# RJ45_Sheet.net
KiCad netlist of a schematic drawn in Altium Designer
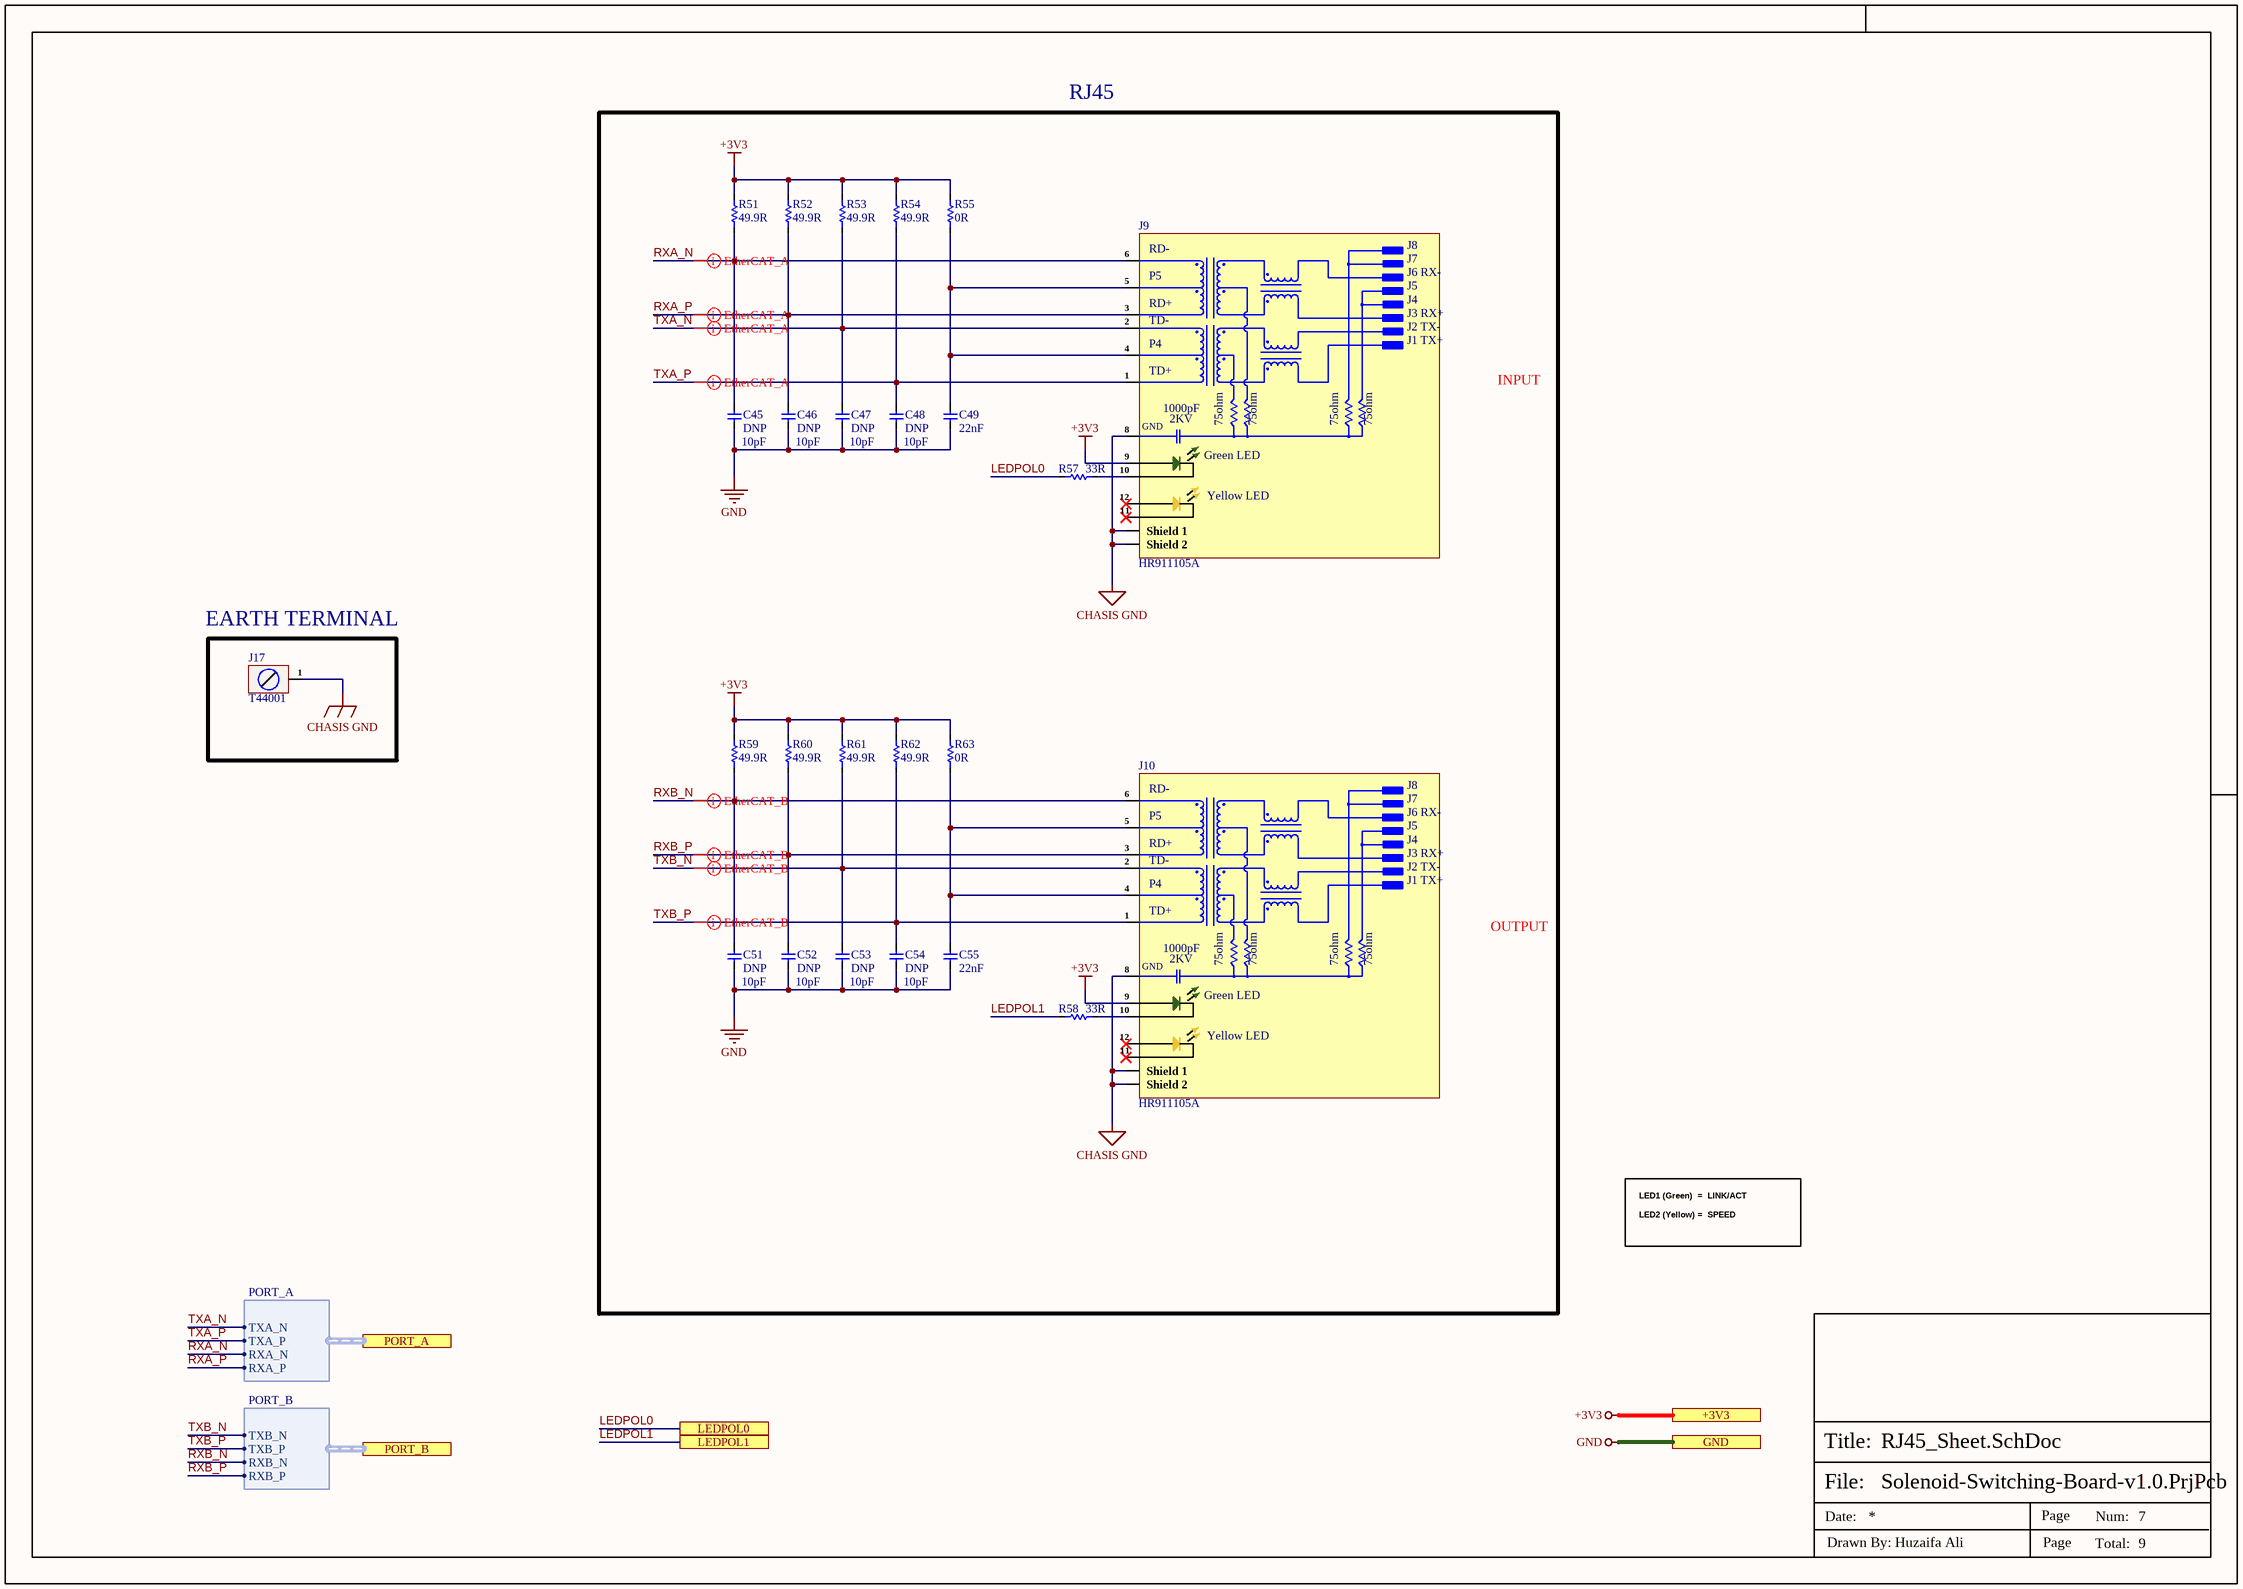
[diagram p0: RJ45_Sheet.SchDoc]

(export (version "E")
  (design (tool "Eeschema 10.0.6"))
  (components
    (comp (ref "C45")
      (value "DNP")
      (footprint "Cap-0402")
      (description "CAP CER 10PF 50V C0G/NP0 0402")
      (fields
        (field (name "MANUFACTURER") "Murata")
        (field (name "MANUFACTURER PART NUMBER") "GRM1555C1H100JA01D")
      )
      (libsource (lib "eSpark Libraries") (part "GRM1555C1H100JA01D"))
    )
    (comp (ref "C46")
      (value "DNP")
      (footprint "Cap-0402")
      (description "CAP CER 10PF 50V C0G/NP0 0402")
      (fields
        (field (name "MANUFACTURER") "Murata")
        (field (name "MANUFACTURER PART NUMBER") "GRM1555C1H100JA01D")
      )
      (libsource (lib "eSpark Libraries") (part "GRM1555C1H100JA01D"))
    )
    (comp (ref "C47")
      (value "DNP")
      (footprint "Cap-0402")
      (description "CAP CER 10PF 50V C0G/NP0 0402")
      (fields
        (field (name "MANUFACTURER") "Murata")
        (field (name "MANUFACTURER PART NUMBER") "GRM1555C1H100JA01D")
      )
      (libsource (lib "eSpark Libraries") (part "GRM1555C1H100JA01D"))
    )
    (comp (ref "C48")
      (value "DNP")
      (footprint "Cap-0402")
      (description "CAP CER 10PF 50V C0G/NP0 0402")
      (fields
        (field (name "MANUFACTURER") "Murata")
        (field (name "MANUFACTURER PART NUMBER") "GRM1555C1H100JA01D")
      )
      (libsource (lib "eSpark Libraries") (part "GRM1555C1H100JA01D"))
    )
    (comp (ref "C49")
      (value "22nF")
      (footprint "Cap-0402")
      (description "CAP CER 0.022UF 16V X7R 0402")
      (fields
        (field (name "MANUFACTURER") "Yageo")
        (field (name "MANUFACTURER PART NUMBER") "CC0402JRX7R7BB223")
      )
      (libsource (lib "eSpark Libraries") (part "CC0402JRX7R7BB223"))
    )
    (comp (ref "C51")
      (value "DNP")
      (footprint "Cap-0402")
      (description "CAP CER 10PF 50V C0G/NP0 0402")
      (fields
        (field (name "MANUFACTURER") "Murata")
        (field (name "MANUFACTURER PART NUMBER") "GRM1555C1H100JA01D")
      )
      (libsource (lib "eSpark Libraries") (part "GRM1555C1H100JA01D"))
    )
    (comp (ref "C52")
      (value "DNP")
      (footprint "Cap-0402")
      (description "CAP CER 10PF 50V C0G/NP0 0402")
      (fields
        (field (name "MANUFACTURER") "Murata")
        (field (name "MANUFACTURER PART NUMBER") "GRM1555C1H100JA01D")
      )
      (libsource (lib "eSpark Libraries") (part "GRM1555C1H100JA01D"))
    )
    (comp (ref "C53")
      (value "DNP")
      (footprint "Cap-0402")
      (description "CAP CER 10PF 50V C0G/NP0 0402")
      (fields
        (field (name "MANUFACTURER") "Murata")
        (field (name "MANUFACTURER PART NUMBER") "GRM1555C1H100JA01D")
      )
      (libsource (lib "eSpark Libraries") (part "GRM1555C1H100JA01D"))
    )
    (comp (ref "C54")
      (value "DNP")
      (footprint "Cap-0402")
      (description "CAP CER 10PF 50V C0G/NP0 0402")
      (fields
        (field (name "MANUFACTURER") "Murata")
        (field (name "MANUFACTURER PART NUMBER") "GRM1555C1H100JA01D")
      )
      (libsource (lib "eSpark Libraries") (part "GRM1555C1H100JA01D"))
    )
    (comp (ref "C55")
      (value "22nF")
      (footprint "Cap-0402")
      (description "CAP CER 0.022UF 16V X7R 0402")
      (fields
        (field (name "MANUFACTURER") "Yageo")
        (field (name "MANUFACTURER PART NUMBER") "CC0402JRX7R7BB223")
      )
      (libsource (lib "eSpark Libraries") (part "CC0402JRX7R7BB223"))
    )
    (comp (ref "J9")
      (value "HR911105A")
      (footprint "HR911105A")
      (description "RJ45 RJReceptacle 1 WithLED Plugin Ethernet Connectors/Modular Connectors (RJ45 RJ11) ROHS")
      (fields (field (name "MANUFACTURER") "HANRUN") (field (name "LCSC PART NUMBER") "C12074"))
      (libsource (lib "eSpark Libraries") (part "HR911105A"))
    )
    (comp (ref "J10")
      (value "HR911105A")
      (footprint "HR911105A")
      (description "RJ45 RJReceptacle 1 WithLED Plugin Ethernet Connectors/Modular Connectors (RJ45 RJ11) ROHS")
      (fields (field (name "MANUFACTURER") "HANRUN") (field (name "LCSC PART NUMBER") "C12074"))
      (libsource (lib "eSpark Libraries") (part "HR911105A"))
    )
    (comp (ref "J17")
      (value "T44001")
      (footprint "T44001")
      (description "M4 Plugin PCB Welding Terminal ROHS")
      (fields (field (name "MANUFACTURER") "XFCN"))
      (libsource (lib "eSpark Libraries") (part "T44001"))
    )
    (comp (ref "R51")
      (value "49.9R")
      (footprint "Res-0603")
      (description "RES 49.9 OHM 1% 1/10W 0603")
      (fields
        (field (name "MANUFACTURER") "Yageo")
        (field (name "MANUFACTURER PART NUMBER") "RC0603FR-0749R9L")
      )
      (libsource (lib "eSpark Libraries") (part "RC0603FR-0749R9L"))
    )
    (comp (ref "R52")
      (value "49.9R")
      (footprint "Res-0603")
      (description "RES 49.9 OHM 1% 1/10W 0603")
      (fields
        (field (name "MANUFACTURER") "Yageo")
        (field (name "MANUFACTURER PART NUMBER") "RC0603FR-0749R9L")
      )
      (libsource (lib "eSpark Libraries") (part "RC0603FR-0749R9L"))
    )
    (comp (ref "R53")
      (value "49.9R")
      (footprint "Res-0603")
      (description "RES 49.9 OHM 1% 1/10W 0603")
      (fields
        (field (name "MANUFACTURER") "Yageo")
        (field (name "MANUFACTURER PART NUMBER") "RC0603FR-0749R9L")
      )
      (libsource (lib "eSpark Libraries") (part "RC0603FR-0749R9L"))
    )
    (comp (ref "R54")
      (value "49.9R")
      (footprint "Res-0603")
      (description "RES 49.9 OHM 1% 1/10W 0603")
      (fields
        (field (name "MANUFACTURER") "Yageo")
        (field (name "MANUFACTURER PART NUMBER") "RC0603FR-0749R9L")
      )
      (libsource (lib "eSpark Libraries") (part "RC0603FR-0749R9L"))
    )
    (comp (ref "R55")
      (value "0R")
      (footprint "Res-0402")
      (description "RESISTOR 0402 JUMPER ZERO OHM")
      (fields
        (field (name "MANUFACTURER") "Yageo")
        (field (name "MANUFACTURER PART NUMBER") "AC0402FR-070RL")
      )
      (libsource (lib "eSpark Libraries") (part "AC0402FR-070RL"))
    )
    (comp (ref "R57")
      (value "33R")
      (footprint "Res-0402")
      (description "RES 33 OHM 1% 1/16W 0402")
      (fields
        (field (name "MANUFACTURER") "Yageo")
        (field (name "MANUFACTURER PART NUMBER") "RC0402FR-0733RL")
      )
      (libsource (lib "eSpark Libraries") (part "RC0402FR-0733RL"))
    )
    (comp (ref "R58")
      (value "33R")
      (footprint "Res-0402")
      (description "RES 33 OHM 1% 1/16W 0402")
      (fields
        (field (name "MANUFACTURER") "Yageo")
        (field (name "MANUFACTURER PART NUMBER") "RC0402FR-0733RL")
      )
      (libsource (lib "eSpark Libraries") (part "RC0402FR-0733RL"))
    )
    (comp (ref "R59")
      (value "49.9R")
      (footprint "Res-0603")
      (description "RES 49.9 OHM 1% 1/10W 0603")
      (fields
        (field (name "MANUFACTURER") "Yageo")
        (field (name "MANUFACTURER PART NUMBER") "RC0603FR-0749R9L")
      )
      (libsource (lib "eSpark Libraries") (part "RC0603FR-0749R9L"))
    )
    (comp (ref "R60")
      (value "49.9R")
      (footprint "Res-0603")
      (description "RES 49.9 OHM 1% 1/10W 0603")
      (fields
        (field (name "MANUFACTURER") "Yageo")
        (field (name "MANUFACTURER PART NUMBER") "RC0603FR-0749R9L")
      )
      (libsource (lib "eSpark Libraries") (part "RC0603FR-0749R9L"))
    )
    (comp (ref "R61")
      (value "49.9R")
      (footprint "Res-0603")
      (description "RES 49.9 OHM 1% 1/10W 0603")
      (fields
        (field (name "MANUFACTURER") "Yageo")
        (field (name "MANUFACTURER PART NUMBER") "RC0603FR-0749R9L")
      )
      (libsource (lib "eSpark Libraries") (part "RC0603FR-0749R9L"))
    )
    (comp (ref "R62")
      (value "49.9R")
      (footprint "Res-0603")
      (description "RES 49.9 OHM 1% 1/10W 0603")
      (fields
        (field (name "MANUFACTURER") "Yageo")
        (field (name "MANUFACTURER PART NUMBER") "RC0603FR-0749R9L")
      )
      (libsource (lib "eSpark Libraries") (part "RC0603FR-0749R9L"))
    )
    (comp (ref "R63")
      (value "0R")
      (footprint "Res-0402")
      (description "RESISTOR 0402 JUMPER ZERO OHM")
      (fields
        (field (name "MANUFACTURER") "Yageo")
        (field (name "MANUFACTURER PART NUMBER") "AC0402FR-070RL")
      )
      (libsource (lib "eSpark Libraries") (part "AC0402FR-070RL"))
    )
  )
  (nets
    (net (code "3") (name "+3V3") (class "Default")
      (node (ref "J10") (pin "9") (pinfunction "ANODE_9") (pintype "passive"))
      (node (ref "J9") (pin "9") (pinfunction "ANODE_9") (pintype "passive"))
      (node (ref "R51") (pin "2") (pinfunction "2_2") (pintype "passive"))
      (node (ref "R52") (pin "2") (pinfunction "2_2") (pintype "passive"))
      (node (ref "R53") (pin "2") (pinfunction "2_2") (pintype "passive"))
      (node (ref "R54") (pin "2") (pinfunction "2_2") (pintype "passive"))
      (node (ref "R55") (pin "2") (pinfunction "2_2") (pintype "passive"))
      (node (ref "R59") (pin "2") (pinfunction "2_2") (pintype "passive"))
      (node (ref "R60") (pin "2") (pinfunction "2_2") (pintype "passive"))
      (node (ref "R61") (pin "2") (pinfunction "2_2") (pintype "passive"))
      (node (ref "R62") (pin "2") (pinfunction "2_2") (pintype "passive"))
      (node (ref "R63") (pin "2") (pinfunction "2_2") (pintype "passive"))
    )
    (net (code "4") (name "/LEDPOL0") (class "Default")
      (node (ref "R57") (pin "1") (pinfunction "1_1") (pintype "passive"))
    )
    (net (code "5") (name "/LEDPOL1") (class "Default")
      (node (ref "R58") (pin "1") (pinfunction "1_1") (pintype "passive"))
    )
    (net (code "6") (name "/RXA_N") (class "Default")
      (node (ref "C45") (pin "2") (pinfunction "2_2") (pintype "passive"))
      (node (ref "J9") (pin "6") (pinfunction "RD-_6") (pintype "passive"))
      (node (ref "R51") (pin "1") (pinfunction "1_1") (pintype "passive"))
    )
    (net (code "7") (name "/RXA_P") (class "Default")
      (node (ref "C46") (pin "2") (pinfunction "2_2") (pintype "passive"))
      (node (ref "J9") (pin "3") (pinfunction "RD+_3") (pintype "passive"))
      (node (ref "R52") (pin "1") (pinfunction "1_1") (pintype "passive"))
    )
    (net (code "8") (name "/RXB_N") (class "Default")
      (node (ref "C51") (pin "2") (pinfunction "2_2") (pintype "passive"))
      (node (ref "J10") (pin "6") (pinfunction "RD-_6") (pintype "passive"))
      (node (ref "R59") (pin "1") (pinfunction "1_1") (pintype "passive"))
    )
    (net (code "9") (name "/RXB_P") (class "Default")
      (node (ref "C52") (pin "2") (pinfunction "2_2") (pintype "passive"))
      (node (ref "J10") (pin "3") (pinfunction "RD+_3") (pintype "passive"))
      (node (ref "R60") (pin "1") (pinfunction "1_1") (pintype "passive"))
    )
    (net (code "10") (name "/TXA_N") (class "Default")
      (node (ref "C47") (pin "2") (pinfunction "2_2") (pintype "passive"))
      (node (ref "J9") (pin "2") (pinfunction "TD-_2") (pintype "passive"))
      (node (ref "R53") (pin "1") (pinfunction "1_1") (pintype "passive"))
    )
    (net (code "11") (name "/TXA_P") (class "Default")
      (node (ref "C48") (pin "2") (pinfunction "2_2") (pintype "passive"))
      (node (ref "J9") (pin "1") (pinfunction "TD+_1") (pintype "passive"))
      (node (ref "R54") (pin "1") (pinfunction "1_1") (pintype "passive"))
    )
    (net (code "12") (name "/TXB_N") (class "Default")
      (node (ref "C53") (pin "2") (pinfunction "2_2") (pintype "passive"))
      (node (ref "J10") (pin "2") (pinfunction "TD-_2") (pintype "passive"))
      (node (ref "R61") (pin "1") (pinfunction "1_1") (pintype "passive"))
    )
    (net (code "13") (name "/TXB_P") (class "Default")
      (node (ref "C54") (pin "2") (pinfunction "2_2") (pintype "passive"))
      (node (ref "J10") (pin "1") (pinfunction "TD+_1") (pintype "passive"))
      (node (ref "R62") (pin "1") (pinfunction "1_1") (pintype "passive"))
    )
    (net (code "16") (name "CHASIS GND") (class "Default")
      (node (ref "J10") (pin "8") (pinfunction "GND_8") (pintype "power_in"))
      (node (ref "J10") (pin "Shield_1") (pinfunction "Shield_1_Shield_1") (pintype "passive"))
      (node (ref "J10") (pin "Shield_2") (pinfunction "Shield_2_Shield_2") (pintype "passive"))
      (node (ref "J17") (pin "1") (pinfunction "1_1") (pintype "passive"))
      (node (ref "J9") (pin "8") (pinfunction "GND_8") (pintype "power_in"))
      (node (ref "J9") (pin "Shield_1") (pinfunction "Shield_1_Shield_1") (pintype "passive"))
      (node (ref "J9") (pin "Shield_2") (pinfunction "Shield_2_Shield_2") (pintype "passive"))
    )
    (net (code "17") (name "GND") (class "Default")
      (node (ref "C45") (pin "1") (pinfunction "1_1") (pintype "passive"))
      (node (ref "C46") (pin "1") (pinfunction "1_1") (pintype "passive"))
      (node (ref "C47") (pin "1") (pinfunction "1_1") (pintype "passive"))
      (node (ref "C48") (pin "1") (pinfunction "1_1") (pintype "passive"))
      (node (ref "C49") (pin "1") (pinfunction "1_1") (pintype "passive"))
      (node (ref "C51") (pin "1") (pinfunction "1_1") (pintype "passive"))
      (node (ref "C52") (pin "1") (pinfunction "1_1") (pintype "passive"))
      (node (ref "C53") (pin "1") (pinfunction "1_1") (pintype "passive"))
      (node (ref "C54") (pin "1") (pinfunction "1_1") (pintype "passive"))
      (node (ref "C55") (pin "1") (pinfunction "1_1") (pintype "passive"))
    )
    (net (code "18") (name "Net-(J9-CATHODE-Pad10)") (class "Default")
      (node (ref "J9") (pin "10") (pinfunction "CATHODE_10") (pintype "passive"))
      (node (ref "R57") (pin "2") (pinfunction "2_2") (pintype "passive"))
    )
    (net (code "19") (name "Net-(J9-P4)") (class "Default")
      (node (ref "C49") (pin "2") (pinfunction "2_2") (pintype "passive"))
      (node (ref "J9") (pin "4") (pinfunction "P4_4") (pintype "passive"))
      (node (ref "J9") (pin "5") (pinfunction "P5_5") (pintype "passive"))
      (node (ref "R55") (pin "1") (pinfunction "1_1") (pintype "passive"))
    )
    (net (code "20") (name "Net-(J10-CATHODE-Pad10)") (class "Default")
      (node (ref "J10") (pin "10") (pinfunction "CATHODE_10") (pintype "passive"))
      (node (ref "R58") (pin "2") (pinfunction "2_2") (pintype "passive"))
    )
    (net (code "21") (name "Net-(J10-P4)") (class "Default")
      (node (ref "C55") (pin "2") (pinfunction "2_2") (pintype "passive"))
      (node (ref "J10") (pin "4") (pinfunction "P4_4") (pintype "passive"))
      (node (ref "J10") (pin "5") (pinfunction "P5_5") (pintype "passive"))
      (node (ref "R63") (pin "1") (pinfunction "1_1") (pintype "passive"))
    )
    (net (code "22") (name "unconnected-(J9-ANODE-Pad12)") (class "Default")
      (node (ref "J9") (pin "12") (pinfunction "ANODE_12") (pintype "passive+no_connect"))
    )
    (net (code "23") (name "unconnected-(J9-CATHODE-Pad11)") (class "Default")
      (node (ref "J9") (pin "11") (pinfunction "CATHODE_11") (pintype "passive+no_connect"))
    )
    (net (code "24") (name "unconnected-(J10-ANODE-Pad12)") (class "Default")
      (node (ref "J10") (pin "12") (pinfunction "ANODE_12") (pintype "passive+no_connect"))
    )
    (net (code "25") (name "unconnected-(J10-CATHODE-Pad11)") (class "Default")
      (node (ref "J10") (pin "11") (pinfunction "CATHODE_11") (pintype "passive+no_connect"))
    )
  )
)
